# 7_can_rc_i2c_analog.net
KiCad netlist of a schematic drawn in Altium Designer
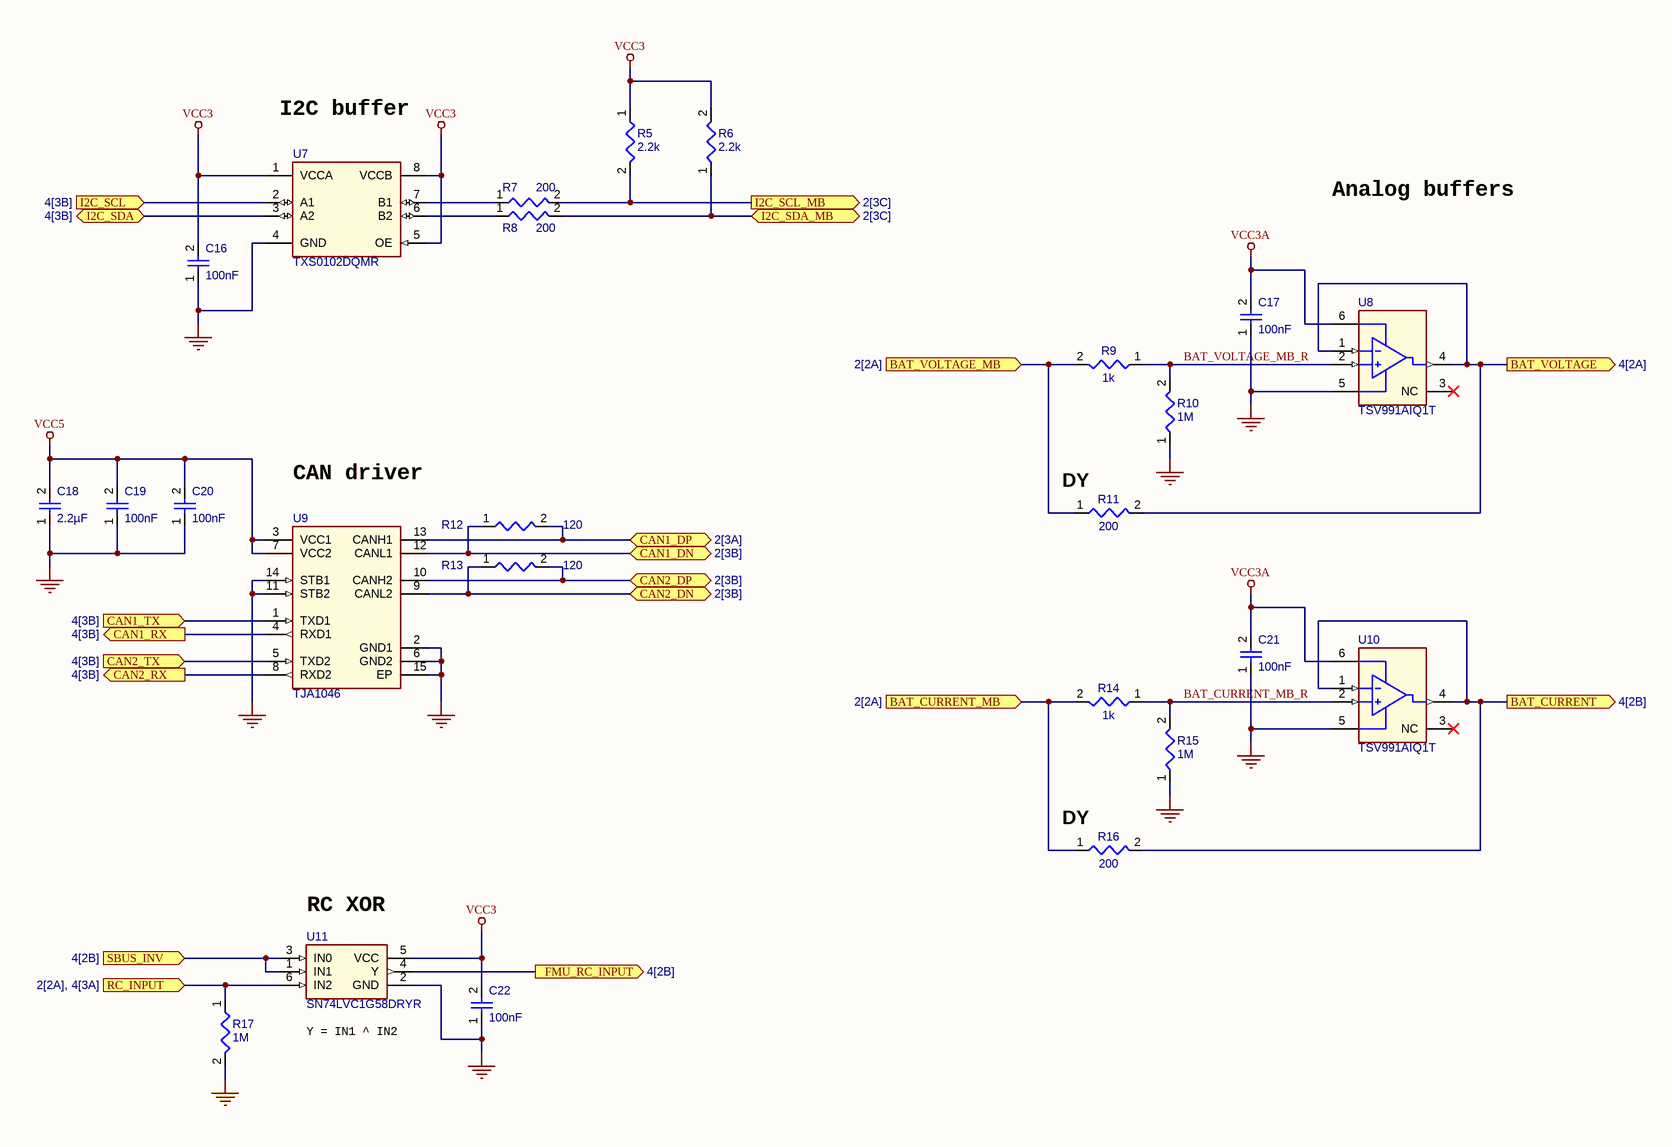
[diagram p0: 7_can_rc_i2c_analog.SchDoc]

(export (version "E")
  (design (tool "Eeschema 10.0.6"))
  (components
    (comp (ref "C16")
      (value "100nF")
      (footprint "CAPC0402(1005)60_L")
      (description "Chip Capacitor, 100nF +/-20%, 10V, 0402, Thickness 0.6 mm")
      (fields (field (name "TOLERANCE") "20%") (field (name "Comment") "Capacitor 100nF +/-20% 10V 0402"))
      (libsource (lib "<Company> Server") (part "CAP-NP-2"))
    )
    (comp (ref "C17")
      (value "100nF")
      (footprint "CAPC0402(1005)60_L")
      (description "Chip Capacitor, 100nF +/-20%, 10V, 0402, Thickness 0.6 mm")
      (fields (field (name "TOLERANCE") "20%") (field (name "Comment") "Capacitor 100nF +/-20% 10V 0402"))
      (libsource (lib "<Company> Server") (part "CAP-NP-2"))
    )
    (comp (ref "C18")
      (value "2.2µF")
      (footprint "CAPC0402(1005)60_L")
      (description "Chip Capacitor, 2,2µF +/-20%, 10V, 0402, Thickness 0.6 mm")
      (fields (field (name "TOLERANCE") "10%") (field (name "Comment") "Capacitor 2,2µF +/-20% 10V 0402"))
      (libsource (lib "<Company> Server") (part "CAP-NP-2"))
    )
    (comp (ref "C19")
      (value "100nF")
      (footprint "CAPC0402(1005)60_L")
      (description "Chip Capacitor, 100nF +/-20%, 10V, 0402, Thickness 0.6 mm")
      (fields (field (name "TOLERANCE") "20%") (field (name "Comment") "Capacitor 100nF +/-20% 10V 0402"))
      (libsource (lib "<Company> Server") (part "CAP-NP-2"))
    )
    (comp (ref "C20")
      (value "100nF")
      (footprint "CAPC0402(1005)60_L")
      (description "Chip Capacitor, 100nF +/-20%, 10V, 0402, Thickness 0.6 mm")
      (fields (field (name "TOLERANCE") "20%") (field (name "Comment") "Capacitor 100nF +/-20% 10V 0402"))
      (libsource (lib "<Company> Server") (part "CAP-NP-2"))
    )
    (comp (ref "C21")
      (value "100nF")
      (footprint "CAPC0402(1005)60_L")
      (description "Chip Capacitor, 100nF +/-20%, 10V, 0402, Thickness 0.6 mm")
      (fields (field (name "TOLERANCE") "20%") (field (name "Comment") "Capacitor 100nF +/-20% 10V 0402"))
      (libsource (lib "<Company> Server") (part "CAP-NP-2"))
    )
    (comp (ref "C22")
      (value "100nF")
      (footprint "CAPC0402(1005)60_L")
      (description "Chip Capacitor, 100nF +/-20%, 10V, 0402, Thickness 0.6 mm")
      (fields (field (name "TOLERANCE") "20%") (field (name "Comment") "Capacitor 100nF +/-20% 10V 0402"))
      (libsource (lib "<Company> Server") (part "CAP-NP-2"))
    )
    (comp (ref "R5")
      (value "2.2k")
      (footprint "RESC0402(1005)_L")
      (description "Chip Resistor, 2,2 kOhms, +/-5 %, 63 mW, -55 to 155 degC, 0402")
      (fields (field (name "POWER") "63mW") (field (name "TOLERANCE") "5%"))
      (libsource (lib "<Company> Server") (part "RES-2"))
    )
    (comp (ref "R6")
      (value "2.2k")
      (footprint "RESC0402(1005)_L")
      (description "Chip Resistor, 2,2 kOhms, +/-5 %, 63 mW, -55 to 155 degC, 0402")
      (fields (field (name "POWER") "63mW") (field (name "TOLERANCE") "5%"))
      (libsource (lib "<Company> Server") (part "RES-2"))
    )
    (comp (ref "R7")
      (value "200")
      (footprint "RESC0402(1005)_L")
      (description "Chip Resistor, 200 Ohms, +/-5 %, 63 mW, -55 to 155 degC, 0402")
      (fields (field (name "POWER") "63mW") (field (name "TOLERANCE") "5%"))
      (libsource (lib "<Company> Server") (part "RES-2"))
    )
    (comp (ref "R8")
      (value "200")
      (footprint "RESC0402(1005)_L")
      (description "Chip Resistor, 200 Ohms, +/-5 %, 63 mW, -55 to 155 degC, 0402")
      (fields (field (name "POWER") "63mW") (field (name "TOLERANCE") "5%"))
      (libsource (lib "<Company> Server") (part "RES-2"))
    )
    (comp (ref "R9")
      (value "1k")
      (footprint "RESC0402(1005)_L")
      (description "Chip Resistor, 1 kOhms, +/-5 %, 63 mW, -55 to 155 degC, 0402")
      (fields (field (name "TOLERANCE") "5%") (field (name "POWER") "63mW"))
      (libsource (lib "<Company> Server") (part "RES-2"))
    )
    (comp (ref "R10")
      (value "1M")
      (footprint "RESC0402(1005)_L")
      (description "Chip Resistor, 1 MOhms, +/-5 %, 63 mW, -55 to 155 degC, 0402")
      (fields (field (name "TOLERANCE") "5%") (field (name "POWER") "63mW"))
      (libsource (lib "<Company> Server") (part "RES-2"))
    )
    (comp (ref "R11")
      (value "200")
      (footprint "RESC0402(1005)_L")
      (description "Chip Resistor, 200 Ohms, +/-5 %, 63 mW, -55 to 155 degC, 0402")
      (fields (field (name "POWER") "63mW") (field (name "TOLERANCE") "5%"))
      (libsource (lib "<Company> Server") (part "RES-2"))
    )
    (comp (ref "R12")
      (value "120")
      (footprint "RESC0603(1608)_L")
      (description "Chip Resistor, 120 Ohms, +/-5 %, 0.1 W, -55 to 155 degC, 0603")
      (fields (field (name "TOLERANCE") "5%") (field (name "POWER") "100mW"))
      (libsource (lib "<Company> Server") (part "RES-2"))
    )
    (comp (ref "R13")
      (value "120")
      (footprint "RESC0603(1608)_L")
      (description "Chip Resistor, 120 Ohms, +/-5 %, 0.1 W, -55 to 155 degC, 0603")
      (fields (field (name "TOLERANCE") "5%") (field (name "POWER") "100mW"))
      (libsource (lib "<Company> Server") (part "RES-2"))
    )
    (comp (ref "R14")
      (value "1k")
      (footprint "RESC0402(1005)_L")
      (description "Chip Resistor, 1 kOhms, +/-5 %, 63 mW, -55 to 155 degC, 0402")
      (fields (field (name "TOLERANCE") "5%") (field (name "POWER") "63mW"))
      (libsource (lib "<Company> Server") (part "RES-2"))
    )
    (comp (ref "R15")
      (value "1M")
      (footprint "RESC0402(1005)_L")
      (description "Chip Resistor, 1 MOhms, +/-5 %, 63 mW, -55 to 155 degC, 0402")
      (fields (field (name "TOLERANCE") "5%") (field (name "POWER") "63mW"))
      (libsource (lib "<Company> Server") (part "RES-2"))
    )
    (comp (ref "R16")
      (value "200")
      (footprint "RESC0402(1005)_L")
      (description "Chip Resistor, 200 Ohms, +/-5 %, 63 mW, -55 to 155 degC, 0402")
      (fields (field (name "POWER") "63mW") (field (name "TOLERANCE") "5%"))
      (libsource (lib "<Company> Server") (part "RES-2"))
    )
    (comp (ref "R17")
      (value "1M")
      (footprint "RESC0402(1005)_L")
      (description "Chip Resistor, 1 MOhms, +/-5 %, 63 mW, -55 to 155 degC, 0402")
      (fields (field (name "TOLERANCE") "5%") (field (name "POWER") "63mW"))
      (libsource (lib "<Company> Server") (part "RES-2"))
    )
    (comp (ref "U7")
      (value "TXS0102DQMR")
      (footprint "DQM")
      (description "IC TRANSLATOR VOLTAGE 8-X2SON")
      (libsource (lib "<Company> Server") (part "CMP-001-0022-1"))
    )
    (comp (ref "U8")
      (value "TSV991AIQ1T")
      (footprint "STM-DFN-8_V")
      (libsource (lib "<Company> Server") (part "CMP-001-0008-5"))
    )
    (comp (ref "U9")
      (value "TJA1046")
      (footprint "NXP-SOT1086-2_L")
      (libsource (lib "<Company> Server") (part "CMP-00180-5"))
    )
    (comp (ref "U10")
      (value "TSV991AIQ1T")
      (footprint "STM-DFN-8_V")
      (libsource (lib "<Company> Server") (part "CMP-001-0008-5"))
    )
    (comp (ref "U11")
      (value "SN74LVC1G58DRYR")
      (footprint "DRY0006A_V")
      (description "CONFIGURABLE MULTIPLE-FUNCTION GATE, DRY0006A, LARGE T&R")
      (libsource (lib "<Company> Server") (part "CMP-00132-5"))
    )
  )
  (nets
    (net (code "1") (name "/BAT_CURRENT") (class "Default")
      (node (ref "R16") (pin "2") (pinfunction "2_2") (pintype "passive"))
      (node (ref "U10") (pin "1") (pinfunction "IN-_1") (pintype "input"))
      (node (ref "U10") (pin "4") (pinfunction "OUT_4") (pintype "output"))
    )
    (net (code "2") (name "/BAT_CURRENT_MB") (class "Default")
      (node (ref "R14") (pin "2") (pinfunction "2_2") (pintype "passive"))
      (node (ref "R16") (pin "1") (pinfunction "1_1") (pintype "passive"))
    )
    (net (code "3") (name "/BAT_CURRENT_MB_R") (class "Default")
      (node (ref "R14") (pin "1") (pinfunction "1_1") (pintype "passive"))
      (node (ref "R15") (pin "2") (pinfunction "2_2") (pintype "passive"))
      (node (ref "U10") (pin "2") (pinfunction "IN+_2") (pintype "input"))
    )
    (net (code "4") (name "/BAT_VOLTAGE") (class "Default")
      (node (ref "R11") (pin "2") (pinfunction "2_2") (pintype "passive"))
      (node (ref "U8") (pin "1") (pinfunction "IN-_1") (pintype "input"))
      (node (ref "U8") (pin "4") (pinfunction "OUT_4") (pintype "output"))
    )
    (net (code "5") (name "/BAT_VOLTAGE_MB") (class "Default")
      (node (ref "R11") (pin "1") (pinfunction "1_1") (pintype "passive"))
      (node (ref "R9") (pin "2") (pinfunction "2_2") (pintype "passive"))
    )
    (net (code "6") (name "/BAT_VOLTAGE_MB_R") (class "Default")
      (node (ref "R10") (pin "2") (pinfunction "2_2") (pintype "passive"))
      (node (ref "R9") (pin "1") (pinfunction "1_1") (pintype "passive"))
      (node (ref "U8") (pin "2") (pinfunction "IN+_2") (pintype "input"))
    )
    (net (code "7") (name "/CAN1_DN") (class "Default")
      (node (ref "R12") (pin "1") (pinfunction "1_1") (pintype "passive"))
      (node (ref "U9") (pin "12") (pinfunction "CANL1_12") (pintype "passive"))
    )
    (net (code "8") (name "/CAN1_DP") (class "Default")
      (node (ref "R12") (pin "2") (pinfunction "2_2") (pintype "passive"))
      (node (ref "U9") (pin "13") (pinfunction "CANH1_13") (pintype "passive"))
    )
    (net (code "9") (name "/CAN1_RX") (class "Default")
      (node (ref "U9") (pin "4") (pinfunction "RXD1_4") (pintype "output"))
    )
    (net (code "10") (name "/CAN1_TX") (class "Default")
      (node (ref "U9") (pin "1") (pinfunction "TXD1_1") (pintype "input"))
    )
    (net (code "11") (name "/CAN2_DN") (class "Default")
      (node (ref "R13") (pin "1") (pinfunction "1_1") (pintype "passive"))
      (node (ref "U9") (pin "9") (pinfunction "CANL2_9") (pintype "passive"))
    )
    (net (code "12") (name "/CAN2_DP") (class "Default")
      (node (ref "R13") (pin "2") (pinfunction "2_2") (pintype "passive"))
      (node (ref "U9") (pin "10") (pinfunction "CANH2_10") (pintype "passive"))
    )
    (net (code "13") (name "/CAN2_RX") (class "Default")
      (node (ref "U9") (pin "8") (pinfunction "RXD2_8") (pintype "output"))
    )
    (net (code "14") (name "/CAN2_TX") (class "Default")
      (node (ref "U9") (pin "5") (pinfunction "TXD2_5") (pintype "input"))
    )
    (net (code "15") (name "/FMU_RC_INPUT") (class "Default")
      (node (ref "U11") (pin "4") (pinfunction "Y_4") (pintype "output"))
    )
    (net (code "16") (name "/I2C_SCL") (class "Default")
      (node (ref "U7") (pin "2") (pinfunction "A1_2") (pintype "bidirectional"))
    )
    (net (code "17") (name "/I2C_SCL_MB") (class "Default")
      (node (ref "R5") (pin "2") (pinfunction "2_2") (pintype "passive"))
      (node (ref "R7") (pin "2") (pinfunction "2_2") (pintype "passive"))
    )
    (net (code "18") (name "/I2C_SDA") (class "Default")
      (node (ref "U7") (pin "3") (pinfunction "A2_3") (pintype "bidirectional"))
    )
    (net (code "19") (name "/I2C_SDA_MB") (class "Default")
      (node (ref "R6") (pin "1") (pinfunction "1_1") (pintype "passive"))
      (node (ref "R8") (pin "2") (pinfunction "2_2") (pintype "passive"))
    )
    (net (code "20") (name "/RC_INPUT") (class "Default")
      (node (ref "R17") (pin "1") (pinfunction "1_1") (pintype "passive"))
      (node (ref "U11") (pin "6") (pinfunction "IN2_6") (pintype "input"))
    )
    (net (code "21") (name "/SBUS_INV") (class "Default")
      (node (ref "U11") (pin "1") (pinfunction "IN1_1") (pintype "input"))
      (node (ref "U11") (pin "3") (pinfunction "IN0_3") (pintype "input"))
    )
    (net (code "22") (name "GND") (class "Default")
      (node (ref "C16") (pin "1") (pinfunction "1_1") (pintype "passive"))
      (node (ref "C17") (pin "1") (pinfunction "1_1") (pintype "passive"))
      (node (ref "C18") (pin "1") (pinfunction "1_1") (pintype "passive"))
      (node (ref "C19") (pin "1") (pinfunction "1_1") (pintype "passive"))
      (node (ref "C20") (pin "1") (pinfunction "1_1") (pintype "passive"))
      (node (ref "C21") (pin "1") (pinfunction "1_1") (pintype "passive"))
      (node (ref "C22") (pin "1") (pinfunction "1_1") (pintype "passive"))
      (node (ref "R10") (pin "1") (pinfunction "1_1") (pintype "passive"))
      (node (ref "R15") (pin "1") (pinfunction "1_1") (pintype "passive"))
      (node (ref "R17") (pin "2") (pinfunction "2_2") (pintype "passive"))
      (node (ref "U10") (pin "5") (pinfunction "VCC-_5") (pintype "power_in"))
      (node (ref "U11") (pin "2") (pinfunction "GND_2") (pintype "power_in"))
      (node (ref "U7") (pin "4") (pinfunction "GND_4") (pintype "power_in"))
      (node (ref "U8") (pin "5") (pinfunction "VCC-_5") (pintype "power_in"))
      (node (ref "U9") (pin "11") (pinfunction "STB2_11") (pintype "input"))
      (node (ref "U9") (pin "14") (pinfunction "STB1_14") (pintype "input"))
      (node (ref "U9") (pin "15") (pinfunction "EP_15") (pintype "power_in"))
      (node (ref "U9") (pin "2") (pinfunction "GND1_2") (pintype "power_in"))
      (node (ref "U9") (pin "6") (pinfunction "GND2_6") (pintype "power_in"))
    )
    (net (code "23") (name "Net-(U7-B1)") (class "Default")
      (node (ref "R7") (pin "1") (pinfunction "1_1") (pintype "passive"))
      (node (ref "U7") (pin "7") (pinfunction "B1_7") (pintype "bidirectional"))
    )
    (net (code "24") (name "Net-(U7-B2)") (class "Default")
      (node (ref "R8") (pin "1") (pinfunction "1_1") (pintype "passive"))
      (node (ref "U7") (pin "6") (pinfunction "B2_6") (pintype "bidirectional"))
    )
    (net (code "25") (name "VCC3") (class "Default")
      (node (ref "C16") (pin "2") (pinfunction "2_2") (pintype "passive"))
      (node (ref "C22") (pin "2") (pinfunction "2_2") (pintype "passive"))
      (node (ref "R5") (pin "1") (pinfunction "1_1") (pintype "passive"))
      (node (ref "R6") (pin "2") (pinfunction "2_2") (pintype "passive"))
      (node (ref "U11") (pin "5") (pinfunction "VCC_5") (pintype "power_in"))
      (node (ref "U7") (pin "1") (pinfunction "VCCA_1") (pintype "power_in"))
      (node (ref "U7") (pin "5") (pinfunction "OE_5") (pintype "input"))
      (node (ref "U7") (pin "8") (pinfunction "VCCB_8") (pintype "power_in"))
    )
    (net (code "26") (name "VCC3A") (class "Default")
      (node (ref "C17") (pin "2") (pinfunction "2_2") (pintype "passive"))
      (node (ref "C21") (pin "2") (pinfunction "2_2") (pintype "passive"))
      (node (ref "U10") (pin "6") (pinfunction "VCC+_6") (pintype "power_in"))
      (node (ref "U8") (pin "6") (pinfunction "VCC+_6") (pintype "power_in"))
    )
    (net (code "27") (name "VCC5") (class "Default")
      (node (ref "C18") (pin "2") (pinfunction "2_2") (pintype "passive"))
      (node (ref "C19") (pin "2") (pinfunction "2_2") (pintype "passive"))
      (node (ref "C20") (pin "2") (pinfunction "2_2") (pintype "passive"))
      (node (ref "U9") (pin "3") (pinfunction "VCC1_3") (pintype "power_in"))
      (node (ref "U9") (pin "7") (pinfunction "VCC2_7") (pintype "power_in"))
    )
    (net (code "28") (name "unconnected-(U8-NC-Pad3)") (class "Default")
      (node (ref "U8") (pin "3") (pinfunction "NC_3") (pintype "passive+no_connect"))
    )
    (net (code "29") (name "unconnected-(U10-NC-Pad3)") (class "Default")
      (node (ref "U10") (pin "3") (pinfunction "NC_3") (pintype "passive+no_connect"))
    )
  )
)
